# mux10-1.net
KiCad netlist of a schematic drawn in Altium Designer
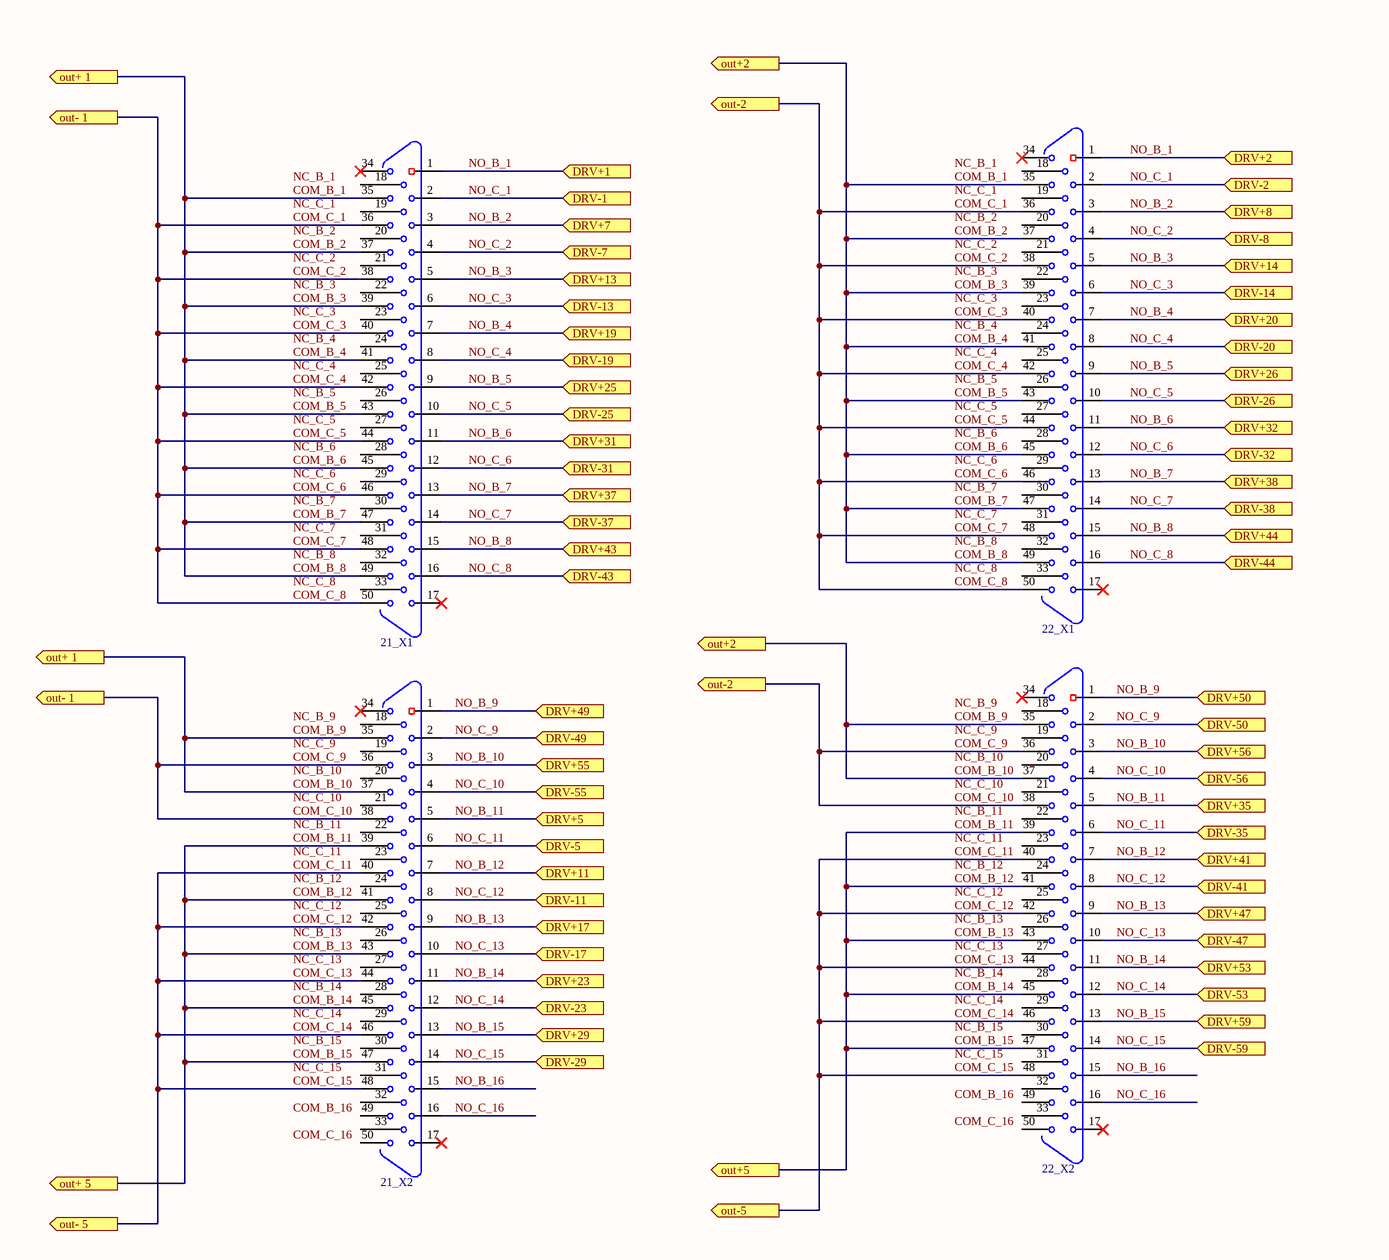
[diagram p0: mux10-1.SchDoc, left]
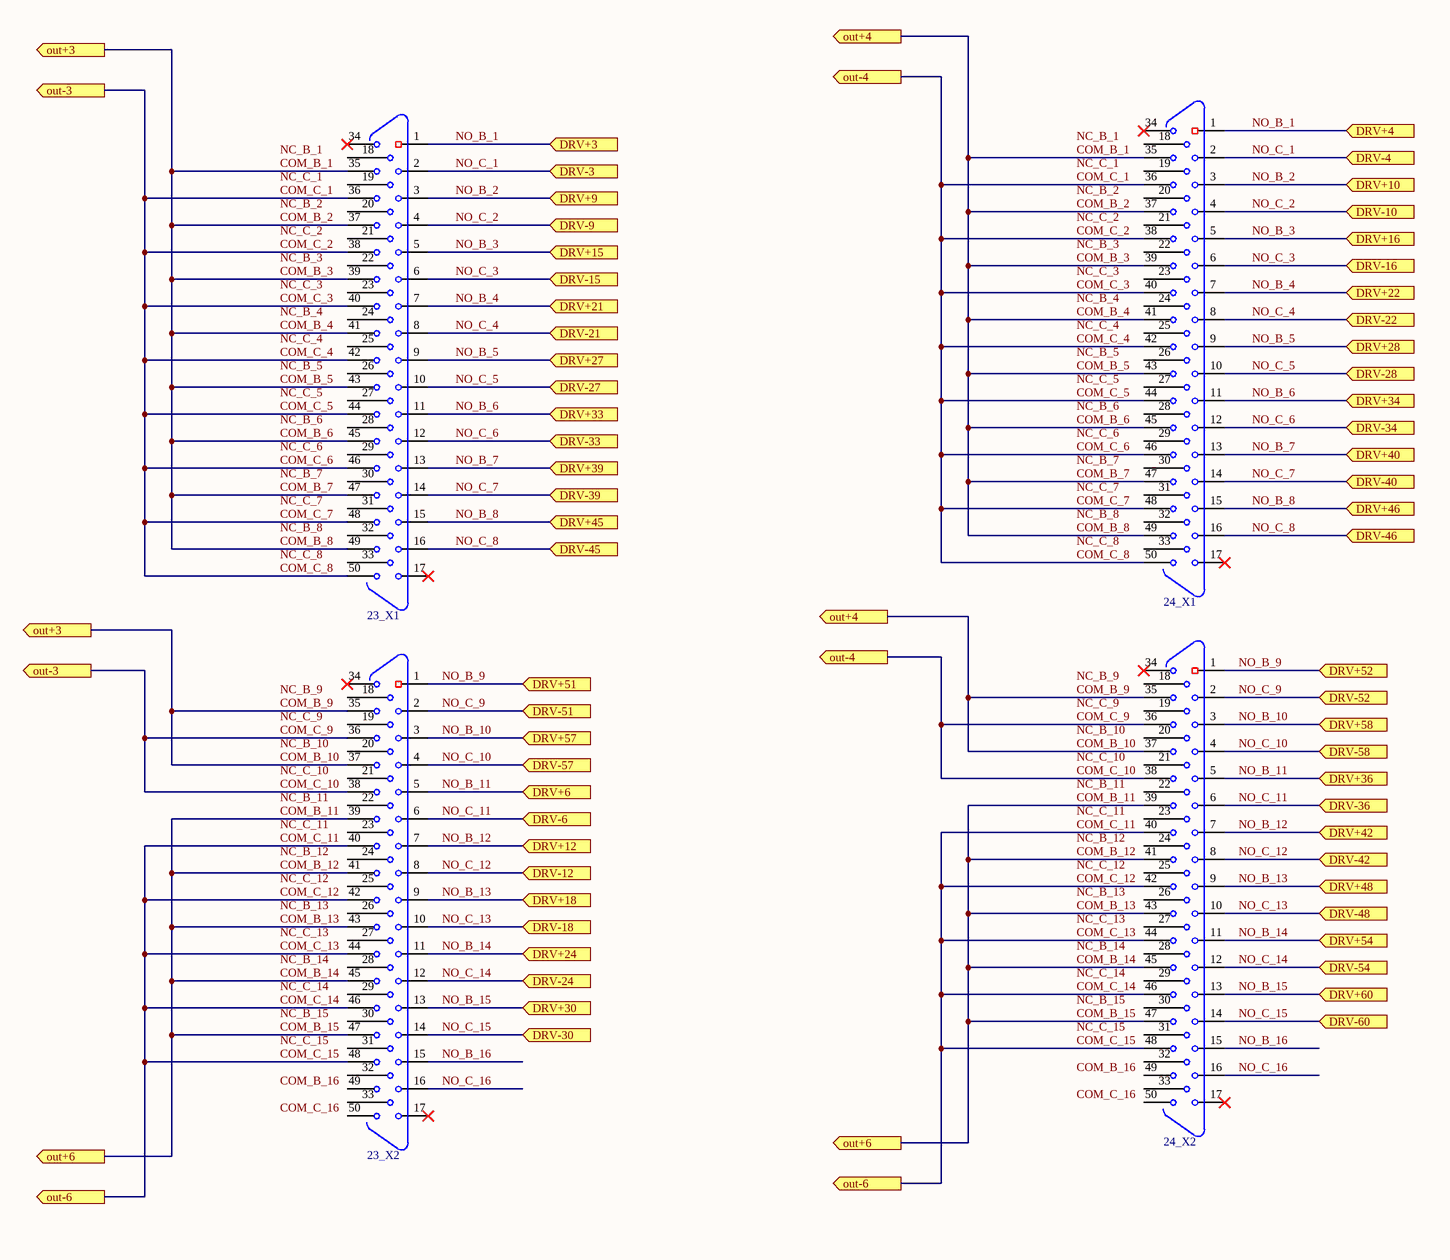
[diagram p1: mux10-1.SchDoc, right]

(export (version "E")
  (design (tool "Eeschema 10.0.6"))
  (components
    (comp (ref "21_X1") (value "DB50") (footprint "DB50_RA") (libsource (lib "WIRE") (part "DB50")))
    (comp (ref "21_X2") (value "DB50") (footprint "DB50_RA") (libsource (lib "WIRE") (part "DB50")))
    (comp (ref "22_X1") (value "DB50") (footprint "DB50_RA") (libsource (lib "WIRE") (part "DB50")))
    (comp (ref "22_X2") (value "DB50") (footprint "DB50_RA") (libsource (lib "WIRE") (part "DB50")))
    (comp (ref "23_X1") (value "DB50") (footprint "DB50_RA") (libsource (lib "WIRE") (part "DB50")))
    (comp (ref "23_X2") (value "DB50") (footprint "DB50_RA") (libsource (lib "WIRE") (part "DB50")))
    (comp (ref "24_X1") (value "DB50") (footprint "DB50_RA") (libsource (lib "WIRE") (part "DB50")))
    (comp (ref "24_X2") (value "DB50") (footprint "DB50_RA") (libsource (lib "WIRE") (part "DB50")))
  )
  (nets
    (net (code "1") (name "/COM_B_1") (class "Default")
      (node (ref "21_X1") (pin "35") (pinfunction "35_35") (pintype "passive"))
      (node (ref "21_X1") (pin "37") (pinfunction "37_37") (pintype "passive"))
      (node (ref "21_X1") (pin "39") (pinfunction "39_39") (pintype "passive"))
      (node (ref "21_X1") (pin "41") (pinfunction "41_41") (pintype "passive"))
      (node (ref "21_X1") (pin "43") (pinfunction "43_43") (pintype "passive"))
      (node (ref "21_X1") (pin "45") (pinfunction "45_45") (pintype "passive"))
      (node (ref "21_X1") (pin "47") (pinfunction "47_47") (pintype "passive"))
      (node (ref "21_X1") (pin "49") (pinfunction "49_49") (pintype "passive"))
      (node (ref "21_X2") (pin "35") (pinfunction "35_35") (pintype "passive"))
      (node (ref "21_X2") (pin "37") (pinfunction "37_37") (pintype "passive"))
      (node (ref "22_X1") (pin "35") (pinfunction "35_35") (pintype "passive"))
      (node (ref "22_X1") (pin "37") (pinfunction "37_37") (pintype "passive"))
      (node (ref "22_X1") (pin "39") (pinfunction "39_39") (pintype "passive"))
      (node (ref "22_X1") (pin "41") (pinfunction "41_41") (pintype "passive"))
      (node (ref "22_X1") (pin "43") (pinfunction "43_43") (pintype "passive"))
      (node (ref "22_X1") (pin "45") (pinfunction "45_45") (pintype "passive"))
      (node (ref "22_X1") (pin "47") (pinfunction "47_47") (pintype "passive"))
      (node (ref "22_X1") (pin "49") (pinfunction "49_49") (pintype "passive"))
      (node (ref "22_X2") (pin "35") (pinfunction "35_35") (pintype "passive"))
      (node (ref "22_X2") (pin "37") (pinfunction "37_37") (pintype "passive"))
      (node (ref "23_X1") (pin "35") (pinfunction "35_35") (pintype "passive"))
      (node (ref "23_X1") (pin "37") (pinfunction "37_37") (pintype "passive"))
      (node (ref "23_X1") (pin "39") (pinfunction "39_39") (pintype "passive"))
      (node (ref "23_X1") (pin "41") (pinfunction "41_41") (pintype "passive"))
      (node (ref "23_X1") (pin "43") (pinfunction "43_43") (pintype "passive"))
      (node (ref "23_X1") (pin "45") (pinfunction "45_45") (pintype "passive"))
      (node (ref "23_X1") (pin "47") (pinfunction "47_47") (pintype "passive"))
      (node (ref "23_X1") (pin "49") (pinfunction "49_49") (pintype "passive"))
      (node (ref "23_X2") (pin "35") (pinfunction "35_35") (pintype "passive"))
      (node (ref "23_X2") (pin "37") (pinfunction "37_37") (pintype "passive"))
      (node (ref "24_X1") (pin "35") (pinfunction "35_35") (pintype "passive"))
      (node (ref "24_X1") (pin "37") (pinfunction "37_37") (pintype "passive"))
      (node (ref "24_X1") (pin "39") (pinfunction "39_39") (pintype "passive"))
      (node (ref "24_X1") (pin "41") (pinfunction "41_41") (pintype "passive"))
      (node (ref "24_X1") (pin "43") (pinfunction "43_43") (pintype "passive"))
      (node (ref "24_X1") (pin "45") (pinfunction "45_45") (pintype "passive"))
      (node (ref "24_X1") (pin "47") (pinfunction "47_47") (pintype "passive"))
      (node (ref "24_X1") (pin "49") (pinfunction "49_49") (pintype "passive"))
      (node (ref "24_X2") (pin "35") (pinfunction "35_35") (pintype "passive"))
      (node (ref "24_X2") (pin "37") (pinfunction "37_37") (pintype "passive"))
    )
    (net (code "2") (name "/COM_B_11") (class "Default")
      (node (ref "21_X2") (pin "39") (pinfunction "39_39") (pintype "passive"))
      (node (ref "21_X2") (pin "41") (pinfunction "41_41") (pintype "passive"))
      (node (ref "21_X2") (pin "43") (pinfunction "43_43") (pintype "passive"))
      (node (ref "21_X2") (pin "45") (pinfunction "45_45") (pintype "passive"))
      (node (ref "21_X2") (pin "47") (pinfunction "47_47") (pintype "passive"))
      (node (ref "22_X2") (pin "39") (pinfunction "39_39") (pintype "passive"))
      (node (ref "22_X2") (pin "41") (pinfunction "41_41") (pintype "passive"))
      (node (ref "22_X2") (pin "43") (pinfunction "43_43") (pintype "passive"))
      (node (ref "22_X2") (pin "45") (pinfunction "45_45") (pintype "passive"))
      (node (ref "22_X2") (pin "47") (pinfunction "47_47") (pintype "passive"))
      (node (ref "23_X2") (pin "39") (pinfunction "39_39") (pintype "passive"))
      (node (ref "23_X2") (pin "41") (pinfunction "41_41") (pintype "passive"))
      (node (ref "23_X2") (pin "43") (pinfunction "43_43") (pintype "passive"))
      (node (ref "23_X2") (pin "45") (pinfunction "45_45") (pintype "passive"))
      (node (ref "23_X2") (pin "47") (pinfunction "47_47") (pintype "passive"))
      (node (ref "24_X2") (pin "39") (pinfunction "39_39") (pintype "passive"))
      (node (ref "24_X2") (pin "41") (pinfunction "41_41") (pintype "passive"))
      (node (ref "24_X2") (pin "43") (pinfunction "43_43") (pintype "passive"))
      (node (ref "24_X2") (pin "45") (pinfunction "45_45") (pintype "passive"))
      (node (ref "24_X2") (pin "47") (pinfunction "47_47") (pintype "passive"))
    )
    (net (code "4") (name "/COM_C_1") (class "Default")
      (node (ref "21_X1") (pin "36") (pinfunction "36_36") (pintype "passive"))
      (node (ref "21_X1") (pin "38") (pinfunction "38_38") (pintype "passive"))
      (node (ref "21_X1") (pin "40") (pinfunction "40_40") (pintype "passive"))
      (node (ref "21_X1") (pin "42") (pinfunction "42_42") (pintype "passive"))
      (node (ref "21_X1") (pin "44") (pinfunction "44_44") (pintype "passive"))
      (node (ref "21_X1") (pin "46") (pinfunction "46_46") (pintype "passive"))
      (node (ref "21_X1") (pin "48") (pinfunction "48_48") (pintype "passive"))
      (node (ref "21_X1") (pin "50") (pinfunction "50_50") (pintype "passive"))
      (node (ref "21_X2") (pin "36") (pinfunction "36_36") (pintype "passive"))
      (node (ref "21_X2") (pin "38") (pinfunction "38_38") (pintype "passive"))
      (node (ref "22_X1") (pin "36") (pinfunction "36_36") (pintype "passive"))
      (node (ref "22_X1") (pin "38") (pinfunction "38_38") (pintype "passive"))
      (node (ref "22_X1") (pin "40") (pinfunction "40_40") (pintype "passive"))
      (node (ref "22_X1") (pin "42") (pinfunction "42_42") (pintype "passive"))
      (node (ref "22_X1") (pin "44") (pinfunction "44_44") (pintype "passive"))
      (node (ref "22_X1") (pin "46") (pinfunction "46_46") (pintype "passive"))
      (node (ref "22_X1") (pin "48") (pinfunction "48_48") (pintype "passive"))
      (node (ref "22_X1") (pin "50") (pinfunction "50_50") (pintype "passive"))
      (node (ref "22_X2") (pin "36") (pinfunction "36_36") (pintype "passive"))
      (node (ref "22_X2") (pin "38") (pinfunction "38_38") (pintype "passive"))
      (node (ref "23_X1") (pin "36") (pinfunction "36_36") (pintype "passive"))
      (node (ref "23_X1") (pin "38") (pinfunction "38_38") (pintype "passive"))
      (node (ref "23_X1") (pin "40") (pinfunction "40_40") (pintype "passive"))
      (node (ref "23_X1") (pin "42") (pinfunction "42_42") (pintype "passive"))
      (node (ref "23_X1") (pin "44") (pinfunction "44_44") (pintype "passive"))
      (node (ref "23_X1") (pin "46") (pinfunction "46_46") (pintype "passive"))
      (node (ref "23_X1") (pin "48") (pinfunction "48_48") (pintype "passive"))
      (node (ref "23_X1") (pin "50") (pinfunction "50_50") (pintype "passive"))
      (node (ref "23_X2") (pin "36") (pinfunction "36_36") (pintype "passive"))
      (node (ref "23_X2") (pin "38") (pinfunction "38_38") (pintype "passive"))
      (node (ref "24_X1") (pin "36") (pinfunction "36_36") (pintype "passive"))
      (node (ref "24_X1") (pin "38") (pinfunction "38_38") (pintype "passive"))
      (node (ref "24_X1") (pin "40") (pinfunction "40_40") (pintype "passive"))
      (node (ref "24_X1") (pin "42") (pinfunction "42_42") (pintype "passive"))
      (node (ref "24_X1") (pin "44") (pinfunction "44_44") (pintype "passive"))
      (node (ref "24_X1") (pin "46") (pinfunction "46_46") (pintype "passive"))
      (node (ref "24_X1") (pin "48") (pinfunction "48_48") (pintype "passive"))
      (node (ref "24_X1") (pin "50") (pinfunction "50_50") (pintype "passive"))
      (node (ref "24_X2") (pin "36") (pinfunction "36_36") (pintype "passive"))
      (node (ref "24_X2") (pin "38") (pinfunction "38_38") (pintype "passive"))
    )
    (net (code "5") (name "/COM_C_11") (class "Default")
      (node (ref "21_X2") (pin "40") (pinfunction "40_40") (pintype "passive"))
      (node (ref "21_X2") (pin "42") (pinfunction "42_42") (pintype "passive"))
      (node (ref "21_X2") (pin "44") (pinfunction "44_44") (pintype "passive"))
      (node (ref "21_X2") (pin "46") (pinfunction "46_46") (pintype "passive"))
      (node (ref "21_X2") (pin "48") (pinfunction "48_48") (pintype "passive"))
      (node (ref "22_X2") (pin "40") (pinfunction "40_40") (pintype "passive"))
      (node (ref "22_X2") (pin "42") (pinfunction "42_42") (pintype "passive"))
      (node (ref "22_X2") (pin "44") (pinfunction "44_44") (pintype "passive"))
      (node (ref "22_X2") (pin "46") (pinfunction "46_46") (pintype "passive"))
      (node (ref "22_X2") (pin "48") (pinfunction "48_48") (pintype "passive"))
      (node (ref "23_X2") (pin "40") (pinfunction "40_40") (pintype "passive"))
      (node (ref "23_X2") (pin "42") (pinfunction "42_42") (pintype "passive"))
      (node (ref "23_X2") (pin "44") (pinfunction "44_44") (pintype "passive"))
      (node (ref "23_X2") (pin "46") (pinfunction "46_46") (pintype "passive"))
      (node (ref "23_X2") (pin "48") (pinfunction "48_48") (pintype "passive"))
      (node (ref "24_X2") (pin "40") (pinfunction "40_40") (pintype "passive"))
      (node (ref "24_X2") (pin "42") (pinfunction "42_42") (pintype "passive"))
      (node (ref "24_X2") (pin "44") (pinfunction "44_44") (pintype "passive"))
      (node (ref "24_X2") (pin "46") (pinfunction "46_46") (pintype "passive"))
      (node (ref "24_X2") (pin "48") (pinfunction "48_48") (pintype "passive"))
    )
    (net (code "37") (name "/NO_B_1") (class "Default")
      (node (ref "21_X1") (pin "1") (pinfunction "1_1") (pintype "passive"))
      (node (ref "22_X1") (pin "1") (pinfunction "1_1") (pintype "passive"))
      (node (ref "23_X1") (pin "1") (pinfunction "1_1") (pintype "passive"))
      (node (ref "24_X1") (pin "1") (pinfunction "1_1") (pintype "passive"))
    )
    (net (code "38") (name "/NO_B_2") (class "Default")
      (node (ref "21_X1") (pin "3") (pinfunction "3_3") (pintype "passive"))
      (node (ref "22_X1") (pin "3") (pinfunction "3_3") (pintype "passive"))
      (node (ref "23_X1") (pin "3") (pinfunction "3_3") (pintype "passive"))
      (node (ref "24_X1") (pin "3") (pinfunction "3_3") (pintype "passive"))
    )
    (net (code "39") (name "/NO_B_3") (class "Default")
      (node (ref "21_X1") (pin "5") (pinfunction "2_5") (pintype "passive"))
      (node (ref "22_X1") (pin "5") (pinfunction "2_5") (pintype "passive"))
      (node (ref "23_X1") (pin "5") (pinfunction "2_5") (pintype "passive"))
      (node (ref "24_X1") (pin "5") (pinfunction "2_5") (pintype "passive"))
    )
    (net (code "40") (name "/NO_B_4") (class "Default")
      (node (ref "21_X1") (pin "7") (pinfunction "7_7") (pintype "passive"))
      (node (ref "22_X1") (pin "7") (pinfunction "7_7") (pintype "passive"))
      (node (ref "23_X1") (pin "7") (pinfunction "7_7") (pintype "passive"))
      (node (ref "24_X1") (pin "7") (pinfunction "7_7") (pintype "passive"))
    )
    (net (code "41") (name "/NO_B_5") (class "Default")
      (node (ref "21_X1") (pin "9") (pinfunction "4_9") (pintype "passive"))
      (node (ref "22_X1") (pin "9") (pinfunction "4_9") (pintype "passive"))
      (node (ref "23_X1") (pin "9") (pinfunction "4_9") (pintype "passive"))
      (node (ref "24_X1") (pin "9") (pinfunction "4_9") (pintype "passive"))
    )
    (net (code "42") (name "/NO_B_6") (class "Default")
      (node (ref "21_X1") (pin "11") (pinfunction "11_11") (pintype "passive"))
      (node (ref "22_X1") (pin "11") (pinfunction "11_11") (pintype "passive"))
      (node (ref "23_X1") (pin "11") (pinfunction "11_11") (pintype "passive"))
      (node (ref "24_X1") (pin "11") (pinfunction "11_11") (pintype "passive"))
    )
    (net (code "43") (name "/NO_B_7") (class "Default")
      (node (ref "21_X1") (pin "13") (pinfunction "13_13") (pintype "passive"))
      (node (ref "22_X1") (pin "13") (pinfunction "13_13") (pintype "passive"))
      (node (ref "23_X1") (pin "13") (pinfunction "13_13") (pintype "passive"))
      (node (ref "24_X1") (pin "13") (pinfunction "13_13") (pintype "passive"))
    )
    (net (code "44") (name "/NO_B_8") (class "Default")
      (node (ref "21_X1") (pin "15") (pinfunction "15_15") (pintype "passive"))
      (node (ref "22_X1") (pin "15") (pinfunction "15_15") (pintype "passive"))
      (node (ref "23_X1") (pin "15") (pinfunction "15_15") (pintype "passive"))
      (node (ref "24_X1") (pin "15") (pinfunction "15_15") (pintype "passive"))
    )
    (net (code "45") (name "/NO_B_9") (class "Default")
      (node (ref "21_X2") (pin "1") (pinfunction "1_1") (pintype "passive"))
      (node (ref "22_X2") (pin "1") (pinfunction "1_1") (pintype "passive"))
      (node (ref "23_X2") (pin "1") (pinfunction "1_1") (pintype "passive"))
      (node (ref "24_X2") (pin "1") (pinfunction "1_1") (pintype "passive"))
    )
    (net (code "46") (name "/NO_B_10") (class "Default")
      (node (ref "21_X2") (pin "3") (pinfunction "3_3") (pintype "passive"))
      (node (ref "22_X2") (pin "3") (pinfunction "3_3") (pintype "passive"))
      (node (ref "23_X2") (pin "3") (pinfunction "3_3") (pintype "passive"))
      (node (ref "24_X2") (pin "3") (pinfunction "3_3") (pintype "passive"))
    )
    (net (code "47") (name "/NO_B_11") (class "Default")
      (node (ref "21_X2") (pin "5") (pinfunction "2_5") (pintype "passive"))
      (node (ref "22_X2") (pin "5") (pinfunction "2_5") (pintype "passive"))
      (node (ref "23_X2") (pin "5") (pinfunction "2_5") (pintype "passive"))
      (node (ref "24_X2") (pin "5") (pinfunction "2_5") (pintype "passive"))
    )
    (net (code "48") (name "/NO_B_12") (class "Default")
      (node (ref "21_X2") (pin "7") (pinfunction "7_7") (pintype "passive"))
      (node (ref "22_X2") (pin "7") (pinfunction "7_7") (pintype "passive"))
      (node (ref "23_X2") (pin "7") (pinfunction "7_7") (pintype "passive"))
      (node (ref "24_X2") (pin "7") (pinfunction "7_7") (pintype "passive"))
    )
    (net (code "49") (name "/NO_B_13") (class "Default")
      (node (ref "21_X2") (pin "9") (pinfunction "4_9") (pintype "passive"))
      (node (ref "22_X2") (pin "9") (pinfunction "4_9") (pintype "passive"))
      (node (ref "23_X2") (pin "9") (pinfunction "4_9") (pintype "passive"))
      (node (ref "24_X2") (pin "9") (pinfunction "4_9") (pintype "passive"))
    )
    (net (code "50") (name "/NO_B_14") (class "Default")
      (node (ref "21_X2") (pin "11") (pinfunction "11_11") (pintype "passive"))
      (node (ref "22_X2") (pin "11") (pinfunction "11_11") (pintype "passive"))
      (node (ref "23_X2") (pin "11") (pinfunction "11_11") (pintype "passive"))
      (node (ref "24_X2") (pin "11") (pinfunction "11_11") (pintype "passive"))
    )
    (net (code "51") (name "/NO_B_15") (class "Default")
      (node (ref "21_X2") (pin "13") (pinfunction "13_13") (pintype "passive"))
      (node (ref "22_X2") (pin "13") (pinfunction "13_13") (pintype "passive"))
      (node (ref "23_X2") (pin "13") (pinfunction "13_13") (pintype "passive"))
      (node (ref "24_X2") (pin "13") (pinfunction "13_13") (pintype "passive"))
    )
    (net (code "52") (name "/NO_B_16") (class "Default")
      (node (ref "21_X2") (pin "15") (pinfunction "15_15") (pintype "passive"))
      (node (ref "22_X2") (pin "15") (pinfunction "15_15") (pintype "passive"))
      (node (ref "23_X2") (pin "15") (pinfunction "15_15") (pintype "passive"))
      (node (ref "24_X2") (pin "15") (pinfunction "15_15") (pintype "passive"))
    )
    (net (code "53") (name "/NO_C_1") (class "Default")
      (node (ref "21_X1") (pin "2") (pinfunction "2_2") (pintype "passive"))
      (node (ref "22_X1") (pin "2") (pinfunction "2_2") (pintype "passive"))
      (node (ref "23_X1") (pin "2") (pinfunction "2_2") (pintype "passive"))
      (node (ref "24_X1") (pin "2") (pinfunction "2_2") (pintype "passive"))
    )
    (net (code "54") (name "/NO_C_2") (class "Default")
      (node (ref "21_X1") (pin "4") (pinfunction "4_4") (pintype "passive"))
      (node (ref "22_X1") (pin "4") (pinfunction "4_4") (pintype "passive"))
      (node (ref "23_X1") (pin "4") (pinfunction "4_4") (pintype "passive"))
      (node (ref "24_X1") (pin "4") (pinfunction "4_4") (pintype "passive"))
    )
    (net (code "55") (name "/NO_C_3") (class "Default")
      (node (ref "21_X1") (pin "6") (pinfunction "6_6") (pintype "passive"))
      (node (ref "22_X1") (pin "6") (pinfunction "6_6") (pintype "passive"))
      (node (ref "23_X1") (pin "6") (pinfunction "6_6") (pintype "passive"))
      (node (ref "24_X1") (pin "6") (pinfunction "6_6") (pintype "passive"))
    )
    (net (code "56") (name "/NO_C_4") (class "Default")
      (node (ref "21_X1") (pin "8") (pinfunction "8_8") (pintype "passive"))
      (node (ref "22_X1") (pin "8") (pinfunction "8_8") (pintype "passive"))
      (node (ref "23_X1") (pin "8") (pinfunction "8_8") (pintype "passive"))
      (node (ref "24_X1") (pin "8") (pinfunction "8_8") (pintype "passive"))
    )
    (net (code "57") (name "/NO_C_5") (class "Default")
      (node (ref "21_X1") (pin "10") (pinfunction "10_10") (pintype "passive"))
      (node (ref "22_X1") (pin "10") (pinfunction "10_10") (pintype "passive"))
      (node (ref "23_X1") (pin "10") (pinfunction "10_10") (pintype "passive"))
      (node (ref "24_X1") (pin "10") (pinfunction "10_10") (pintype "passive"))
    )
    (net (code "58") (name "/NO_C_6") (class "Default")
      (node (ref "21_X1") (pin "12") (pinfunction "12_12") (pintype "passive"))
      (node (ref "22_X1") (pin "12") (pinfunction "12_12") (pintype "passive"))
      (node (ref "23_X1") (pin "12") (pinfunction "12_12") (pintype "passive"))
      (node (ref "24_X1") (pin "12") (pinfunction "12_12") (pintype "passive"))
    )
    (net (code "59") (name "/NO_C_7") (class "Default")
      (node (ref "21_X1") (pin "14") (pinfunction "14_14") (pintype "passive"))
      (node (ref "22_X1") (pin "14") (pinfunction "14_14") (pintype "passive"))
      (node (ref "23_X1") (pin "14") (pinfunction "14_14") (pintype "passive"))
      (node (ref "24_X1") (pin "14") (pinfunction "14_14") (pintype "passive"))
    )
    (net (code "60") (name "/NO_C_8") (class "Default")
      (node (ref "21_X1") (pin "16") (pinfunction "16_16") (pintype "passive"))
      (node (ref "22_X1") (pin "16") (pinfunction "16_16") (pintype "passive"))
      (node (ref "23_X1") (pin "16") (pinfunction "16_16") (pintype "passive"))
      (node (ref "24_X1") (pin "16") (pinfunction "16_16") (pintype "passive"))
    )
    (net (code "61") (name "/NO_C_9") (class "Default")
      (node (ref "21_X2") (pin "2") (pinfunction "2_2") (pintype "passive"))
      (node (ref "22_X2") (pin "2") (pinfunction "2_2") (pintype "passive"))
      (node (ref "23_X2") (pin "2") (pinfunction "2_2") (pintype "passive"))
      (node (ref "24_X2") (pin "2") (pinfunction "2_2") (pintype "passive"))
    )
    (net (code "62") (name "/NO_C_10") (class "Default")
      (node (ref "21_X2") (pin "4") (pinfunction "4_4") (pintype "passive"))
      (node (ref "22_X2") (pin "4") (pinfunction "4_4") (pintype "passive"))
      (node (ref "23_X2") (pin "4") (pinfunction "4_4") (pintype "passive"))
      (node (ref "24_X2") (pin "4") (pinfunction "4_4") (pintype "passive"))
    )
    (net (code "63") (name "/NO_C_11") (class "Default")
      (node (ref "21_X2") (pin "6") (pinfunction "6_6") (pintype "passive"))
      (node (ref "22_X2") (pin "6") (pinfunction "6_6") (pintype "passive"))
      (node (ref "23_X2") (pin "6") (pinfunction "6_6") (pintype "passive"))
      (node (ref "24_X2") (pin "6") (pinfunction "6_6") (pintype "passive"))
    )
    (net (code "64") (name "/NO_C_12") (class "Default")
      (node (ref "21_X2") (pin "8") (pinfunction "8_8") (pintype "passive"))
      (node (ref "22_X2") (pin "8") (pinfunction "8_8") (pintype "passive"))
      (node (ref "23_X2") (pin "8") (pinfunction "8_8") (pintype "passive"))
      (node (ref "24_X2") (pin "8") (pinfunction "8_8") (pintype "passive"))
    )
    (net (code "65") (name "/NO_C_13") (class "Default")
      (node (ref "21_X2") (pin "10") (pinfunction "10_10") (pintype "passive"))
      (node (ref "22_X2") (pin "10") (pinfunction "10_10") (pintype "passive"))
      (node (ref "23_X2") (pin "10") (pinfunction "10_10") (pintype "passive"))
      (node (ref "24_X2") (pin "10") (pinfunction "10_10") (pintype "passive"))
    )
    (net (code "66") (name "/NO_C_14") (class "Default")
      (node (ref "21_X2") (pin "12") (pinfunction "12_12") (pintype "passive"))
      (node (ref "22_X2") (pin "12") (pinfunction "12_12") (pintype "passive"))
      (node (ref "23_X2") (pin "12") (pinfunction "12_12") (pintype "passive"))
      (node (ref "24_X2") (pin "12") (pinfunction "12_12") (pintype "passive"))
    )
    (net (code "67") (name "/NO_C_15") (class "Default")
      (node (ref "21_X2") (pin "14") (pinfunction "14_14") (pintype "passive"))
      (node (ref "22_X2") (pin "14") (pinfunction "14_14") (pintype "passive"))
      (node (ref "23_X2") (pin "14") (pinfunction "14_14") (pintype "passive"))
      (node (ref "24_X2") (pin "14") (pinfunction "14_14") (pintype "passive"))
    )
    (net (code "68") (name "/NO_C_16") (class "Default")
      (node (ref "21_X2") (pin "16") (pinfunction "16_16") (pintype "passive"))
      (node (ref "22_X2") (pin "16") (pinfunction "16_16") (pintype "passive"))
      (node (ref "23_X2") (pin "16") (pinfunction "16_16") (pintype "passive"))
      (node (ref "24_X2") (pin "16") (pinfunction "16_16") (pintype "passive"))
    )
    (net (code "69") (name "unconnected-(21_X1-3-Pad25)") (class "Default")
      (node (ref "21_X1") (pin "25") (pinfunction "3_25") (pintype "passive"))
    )
    (net (code "70") (name "unconnected-(21_X1-7-Pad24)") (class "Default")
      (node (ref "21_X1") (pin "24") (pinfunction "7_24") (pintype "passive"))
    )
    (net (code "71") (name "unconnected-(21_X1-Pad17)") (class "Default")
      (node (ref "21_X1") (pin "17") (pinfunction "17_17") (pintype "passive+no_connect"))
    )
    (net (code "72") (name "unconnected-(21_X1-Pad18)") (class "Default")
      (node (ref "21_X1") (pin "18") (pinfunction "18_18") (pintype "passive"))
    )
    (net (code "73") (name "unconnected-(21_X1-Pad19)") (class "Default")
      (node (ref "21_X1") (pin "19") (pinfunction "19_19") (pintype "passive"))
    )
    (net (code "74") (name "unconnected-(21_X1-Pad20)") (class "Default")
      (node (ref "21_X1") (pin "20") (pinfunction "20_20") (pintype "passive"))
    )
    (net (code "75") (name "unconnected-(21_X1-Pad21)") (class "Default")
      (node (ref "21_X1") (pin "21") (pinfunction "21_21") (pintype "passive"))
    )
    (net (code "76") (name "unconnected-(21_X1-Pad22)") (class "Default")
      (node (ref "21_X1") (pin "22") (pinfunction "22_22") (pintype "passive"))
    )
    (net (code "77") (name "unconnected-(21_X1-Pad23)") (class "Default")
      (node (ref "21_X1") (pin "23") (pinfunction "23_23") (pintype "passive"))
    )
    (net (code "78") (name "unconnected-(21_X1-Pad26)") (class "Default")
      (node (ref "21_X1") (pin "26") (pinfunction "26_26") (pintype "passive"))
    )
    (net (code "79") (name "unconnected-(21_X1-Pad27)") (class "Default")
      (node (ref "21_X1") (pin "27") (pinfunction "27_27") (pintype "passive"))
    )
    (net (code "80") (name "unconnected-(21_X1-Pad28)") (class "Default")
      (node (ref "21_X1") (pin "28") (pinfunction "28_28") (pintype "passive"))
    )
    (net (code "81") (name "unconnected-(21_X1-Pad29)") (class "Default")
      (node (ref "21_X1") (pin "29") (pinfunction "29_29") (pintype "passive"))
    )
    (net (code "82") (name "unconnected-(21_X1-Pad30)") (class "Default")
      (node (ref "21_X1") (pin "30") (pinfunction "30_30") (pintype "passive"))
    )
    (net (code "83") (name "unconnected-(21_X1-Pad31)") (class "Default")
      (node (ref "21_X1") (pin "31") (pinfunction "31_31") (pintype "passive"))
    )
    (net (code "84") (name "unconnected-(21_X1-Pad32)") (class "Default")
      (node (ref "21_X1") (pin "32") (pinfunction "32_32") (pintype "passive"))
    )
    (net (code "85") (name "unconnected-(21_X1-Pad33)") (class "Default")
      (node (ref "21_X1") (pin "33") (pinfunction "33_33") (pintype "passive"))
    )
    (net (code "86") (name "unconnected-(21_X1-Pad34)") (class "Default")
      (node (ref "21_X1") (pin "34") (pinfunction "34_34") (pintype "passive+no_connect"))
    )
    (net (code "87") (name "unconnected-(21_X2-3-Pad25)") (class "Default")
      (node (ref "21_X2") (pin "25") (pinfunction "3_25") (pintype "passive"))
    )
    (net (code "88") (name "unconnected-(21_X2-7-Pad24)") (class "Default")
      (node (ref "21_X2") (pin "24") (pinfunction "7_24") (pintype "passive"))
    )
    (net (code "89") (name "unconnected-(21_X2-Pad17)") (class "Default")
      (node (ref "21_X2") (pin "17") (pinfunction "17_17") (pintype "passive+no_connect"))
    )
    (net (code "90") (name "unconnected-(21_X2-Pad18)") (class "Default")
      (node (ref "21_X2") (pin "18") (pinfunction "18_18") (pintype "passive"))
    )
    (net (code "91") (name "unconnected-(21_X2-Pad19)") (class "Default")
      (node (ref "21_X2") (pin "19") (pinfunction "19_19") (pintype "passive"))
    )
    (net (code "92") (name "unconnected-(21_X2-Pad20)") (class "Default")
      (node (ref "21_X2") (pin "20") (pinfunction "20_20") (pintype "passive"))
    )
    (net (code "93") (name "unconnected-(21_X2-Pad21)") (class "Default")
      (node (ref "21_X2") (pin "21") (pinfunction "21_21") (pintype "passive"))
    )
    (net (code "94") (name "unconnected-(21_X2-Pad22)") (class "Default")
      (node (ref "21_X2") (pin "22") (pinfunction "22_22") (pintype "passive"))
    )
    (net (code "95") (name "unconnected-(21_X2-Pad23)") (class "Default")
      (node (ref "21_X2") (pin "23") (pinfunction "23_23") (pintype "passive"))
    )
    (net (code "96") (name "unconnected-(21_X2-Pad26)") (class "Default")
      (node (ref "21_X2") (pin "26") (pinfunction "26_26") (pintype "passive"))
    )
    (net (code "97") (name "unconnected-(21_X2-Pad27)") (class "Default")
      (node (ref "21_X2") (pin "27") (pinfunction "27_27") (pintype "passive"))
    )
    (net (code "98") (name "unconnected-(21_X2-Pad28)") (class "Default")
      (node (ref "21_X2") (pin "28") (pinfunction "28_28") (pintype "passive"))
    )
    (net (code "99") (name "unconnected-(21_X2-Pad29)") (class "Default")
      (node (ref "21_X2") (pin "29") (pinfunction "29_29") (pintype "passive"))
    )
    (net (code "100") (name "unconnected-(21_X2-Pad30)") (class "Default")
      (node (ref "21_X2") (pin "30") (pinfunction "30_30") (pintype "passive"))
    )
    (net (code "101") (name "unconnected-(21_X2-Pad31)") (class "Default")
      (node (ref "21_X2") (pin "31") (pinfunction "31_31") (pintype "passive"))
    )
    (net (code "102") (name "unconnected-(21_X2-Pad32)") (class "Default")
      (node (ref "21_X2") (pin "32") (pinfunction "32_32") (pintype "passive"))
    )
    (net (code "103") (name "unconnected-(21_X2-Pad33)") (class "Default")
      (node (ref "21_X2") (pin "33") (pinfunction "33_33") (pintype "passive"))
    )
    (net (code "104") (name "unconnected-(21_X2-Pad34)") (class "Default")
      (node (ref "21_X2") (pin "34") (pinfunction "34_34") (pintype "passive+no_connect"))
    )
    (net (code "105") (name "unconnected-(21_X2-Pad49)") (class "Default")
      (node (ref "21_X2") (pin "49") (pinfunction "49_49") (pintype "passive"))
    )
    (net (code "106") (name "unconnected-(21_X2-Pad50)") (class "Default")
      (node (ref "21_X2") (pin "50") (pinfunction "50_50") (pintype "passive"))
    )
    (net (code "107") (name "unconnected-(22_X1-3-Pad25)") (class "Default")
      (node (ref "22_X1") (pin "25") (pinfunction "3_25") (pintype "passive"))
    )
    (net (code "108") (name "unconnected-(22_X1-7-Pad24)") (class "Default")
      (node (ref "22_X1") (pin "24") (pinfunction "7_24") (pintype "passive"))
    )
    (net (code "109") (name "unconnected-(22_X1-Pad17)") (class "Default")
      (node (ref "22_X1") (pin "17") (pinfunction "17_17") (pintype "passive+no_connect"))
    )
    (net (code "110") (name "unconnected-(22_X1-Pad18)") (class "Default")
      (node (ref "22_X1") (pin "18") (pinfunction "18_18") (pintype "passive"))
    )
    (net (code "111") (name "unconnected-(22_X1-Pad19)") (class "Default")
      (node (ref "22_X1") (pin "19") (pinfunction "19_19") (pintype "passive"))
    )
    (net (code "112") (name "unconnected-(22_X1-Pad20)") (class "Default")
      (node (ref "22_X1") (pin "20") (pinfunction "20_20") (pintype "passive"))
    )
    (net (code "113") (name "unconnected-(22_X1-Pad21)") (class "Default")
      (node (ref "22_X1") (pin "21") (pinfunction "21_21") (pintype "passive"))
    )
    (net (code "114") (name "unconnected-(22_X1-Pad22)") (class "Default")
      (node (ref "22_X1") (pin "22") (pinfunction "22_22") (pintype "passive"))
    )
    (net (code "115") (name "unconnected-(22_X1-Pad23)") (class "Default")
      (node (ref "22_X1") (pin "23") (pinfunction "23_23") (pintype "passive"))
    )
    (net (code "116") (name "unconnected-(22_X1-Pad26)") (class "Default")
      (node (ref "22_X1") (pin "26") (pinfunction "26_26") (pintype "passive"))
    )
    (net (code "117") (name "unconnected-(22_X1-Pad27)") (class "Default")
      (node (ref "22_X1") (pin "27") (pinfunction "27_27") (pintype "passive"))
    )
    (net (code "118") (name "unconnected-(22_X1-Pad28)") (class "Default")
      (node (ref "22_X1") (pin "28") (pinfunction "28_28") (pintype "passive"))
    )
    (net (code "119") (name "unconnected-(22_X1-Pad29)") (class "Default")
      (node (ref "22_X1") (pin "29") (pinfunction "29_29") (pintype "passive"))
    )
    (net (code "120") (name "unconnected-(22_X1-Pad30)") (class "Default")
      (node (ref "22_X1") (pin "30") (pinfunction "30_30") (pintype "passive"))
    )
    (net (code "121") (name "unconnected-(22_X1-Pad31)") (class "Default")
      (node (ref "22_X1") (pin "31") (pinfunction "31_31") (pintype "passive"))
    )
    (net (code "122") (name "unconnected-(22_X1-Pad32)") (class "Default")
      (node (ref "22_X1") (pin "32") (pinfunction "32_32") (pintype "passive"))
    )
    (net (code "123") (name "unconnected-(22_X1-Pad33)") (class "Default")
      (node (ref "22_X1") (pin "33") (pinfunction "33_33") (pintype "passive"))
    )
    (net (code "124") (name "unconnected-(22_X1-Pad34)") (class "Default")
      (node (ref "22_X1") (pin "34") (pinfunction "34_34") (pintype "passive+no_connect"))
    )
    (net (code "125") (name "unconnected-(22_X2-3-Pad25)") (class "Default")
      (node (ref "22_X2") (pin "25") (pinfunction "3_25") (pintype "passive"))
    )
    (net (code "126") (name "unconnected-(22_X2-7-Pad24)") (class "Default")
      (node (ref "22_X2") (pin "24") (pinfunction "7_24") (pintype "passive"))
    )
    (net (code "127") (name "unconnected-(22_X2-Pad17)") (class "Default")
      (node (ref "22_X2") (pin "17") (pinfunction "17_17") (pintype "passive+no_connect"))
    )
    (net (code "128") (name "unconnected-(22_X2-Pad18)") (class "Default")
      (node (ref "22_X2") (pin "18") (pinfunction "18_18") (pintype "passive"))
    )
    (net (code "129") (name "unconnected-(22_X2-Pad19)") (class "Default")
      (node (ref "22_X2") (pin "19") (pinfunction "19_19") (pintype "passive"))
    )
    (net (code "130") (name "unconnected-(22_X2-Pad20)") (class "Default")
      (node (ref "22_X2") (pin "20") (pinfunction "20_20") (pintype "passive"))
    )
    (net (code "131") (name "unconnected-(22_X2-Pad21)") (class "Default")
      (node (ref "22_X2") (pin "21") (pinfunction "21_21") (pintype "passive"))
    )
    (net (code "132") (name "unconnected-(22_X2-Pad22)") (class "Default")
      (node (ref "22_X2") (pin "22") (pinfunction "22_22") (pintype "passive"))
    )
    (net (code "133") (name "unconnected-(22_X2-Pad23)") (class "Default")
      (node (ref "22_X2") (pin "23") (pinfunction "23_23") (pintype "passive"))
    )
    (net (code "134") (name "unconnected-(22_X2-Pad26)") (class "Default")
      (node (ref "22_X2") (pin "26") (pinfunction "26_26") (pintype "passive"))
    )
    (net (code "135") (name "unconnected-(22_X2-Pad27)") (class "Default")
      (node (ref "22_X2") (pin "27") (pinfunction "27_27") (pintype "passive"))
    )
    (net (code "136") (name "unconnected-(22_X2-Pad28)") (class "Default")
      (node (ref "22_X2") (pin "28") (pinfunction "28_28") (pintype "passive"))
    )
    (net (code "137") (name "unconnected-(22_X2-Pad29)") (class "Default")
      (node (ref "22_X2") (pin "29") (pinfunction "29_29") (pintype "passive"))
    )
    (net (code "138") (name "unconnected-(22_X2-Pad30)") (class "Default")
      (node (ref "22_X2") (pin "30") (pinfunction "30_30") (pintype "passive"))
    )
    (net (code "139") (name "unconnected-(22_X2-Pad31)") (class "Default")
      (node (ref "22_X2") (pin "31") (pinfunction "31_31") (pintype "passive"))
    )
    (net (code "140") (name "unconnected-(22_X2-Pad32)") (class "Default")
      (node (ref "22_X2") (pin "32") (pinfunction "32_32") (pintype "passive"))
    )
    (net (code "141") (name "unconnected-(22_X2-Pad33)") (class "Default")
      (node (ref "22_X2") (pin "33") (pinfunction "33_33") (pintype "passive"))
    )
    (net (code "142") (name "unconnected-(22_X2-Pad34)") (class "Default")
      (node (ref "22_X2") (pin "34") (pinfunction "34_34") (pintype "passive+no_connect"))
    )
    (net (code "143") (name "unconnected-(22_X2-Pad49)") (class "Default")
      (node (ref "22_X2") (pin "49") (pinfunction "49_49") (pintype "passive"))
    )
    (net (code "144") (name "unconnected-(22_X2-Pad50)") (class "Default")
      (node (ref "22_X2") (pin "50") (pinfunction "50_50") (pintype "passive"))
    )
    (net (code "145") (name "unconnected-(23_X1-3-Pad25)") (class "Default")
      (node (ref "23_X1") (pin "25") (pinfunction "3_25") (pintype "passive"))
    )
    (net (code "146") (name "unconnected-(23_X1-7-Pad24)") (class "Default")
      (node (ref "23_X1") (pin "24") (pinfunction "7_24") (pintype "passive"))
    )
    (net (code "147") (name "unconnected-(23_X1-Pad17)") (class "Default")
      (node (ref "23_X1") (pin "17") (pinfunction "17_17") (pintype "passive+no_connect"))
    )
    (net (code "148") (name "unconnected-(23_X1-Pad18)") (class "Default")
      (node (ref "23_X1") (pin "18") (pinfunction "18_18") (pintype "passive"))
    )
    (net (code "149") (name "unconnected-(23_X1-Pad19)") (class "Default")
      (node (ref "23_X1") (pin "19") (pinfunction "19_19") (pintype "passive"))
    )
    (net (code "150") (name "unconnected-(23_X1-Pad20)") (class "Default")
      (node (ref "23_X1") (pin "20") (pinfunction "20_20") (pintype "passive"))
    )
    (net (code "151") (name "unconnected-(23_X1-Pad21)") (class "Default")
      (node (ref "23_X1") (pin "21") (pinfunction "21_21") (pintype "passive"))
    )
    (net (code "152") (name "unconnected-(23_X1-Pad22)") (class "Default")
      (node (ref "23_X1") (pin "22") (pinfunction "22_22") (pintype "passive"))
    )
    (net (code "153") (name "unconnected-(23_X1-Pad23)") (class "Default")
      (node (ref "23_X1") (pin "23") (pinfunction "23_23") (pintype "passive"))
    )
    (net (code "154") (name "unconnected-(23_X1-Pad26)") (class "Default")
      (node (ref "23_X1") (pin "26") (pinfunction "26_26") (pintype "passive"))
    )
    (net (code "155") (name "unconnected-(23_X1-Pad27)") (class "Default")
      (node (ref "23_X1") (pin "27") (pinfunction "27_27") (pintype "passive"))
    )
    (net (code "156") (name "unconnected-(23_X1-Pad28)") (class "Default")
      (node (ref "23_X1") (pin "28") (pinfunction "28_28") (pintype "passive"))
    )
    (net (code "157") (name "unconnected-(23_X1-Pad29)") (class "Default")
      (node (ref "23_X1") (pin "29") (pinfunction "29_29") (pintype "passive"))
    )
    (net (code "158") (name "unconnected-(23_X1-Pad30)") (class "Default")
      (node (ref "23_X1") (pin "30") (pinfunction "30_30") (pintype "passive"))
    )
    (net (code "159") (name "unconnected-(23_X1-Pad31)") (class "Default")
      (node (ref "23_X1") (pin "31") (pinfunction "31_31") (pintype "passive"))
    )
    (net (code "160") (name "unconnected-(23_X1-Pad32)") (class "Default")
      (node (ref "23_X1") (pin "32") (pinfunction "32_32") (pintype "passive"))
    )
    (net (code "161") (name "unconnected-(23_X1-Pad33)") (class "Default")
      (node (ref "23_X1") (pin "33") (pinfunction "33_33") (pintype "passive"))
    )
    (net (code "162") (name "unconnected-(23_X1-Pad34)") (class "Default")
      (node (ref "23_X1") (pin "34") (pinfunction "34_34") (pintype "passive+no_connect"))
    )
    (net (code "163") (name "unconnected-(23_X2-3-Pad25)") (class "Default")
      (node (ref "23_X2") (pin "25") (pinfunction "3_25") (pintype "passive"))
    )
    (net (code "164") (name "unconnected-(23_X2-7-Pad24)") (class "Default")
      (node (ref "23_X2") (pin "24") (pinfunction "7_24") (pintype "passive"))
    )
    (net (code "165") (name "unconnected-(23_X2-Pad17)") (class "Default")
      (node (ref "23_X2") (pin "17") (pinfunction "17_17") (pintype "passive+no_connect"))
    )
    (net (code "166") (name "unconnected-(23_X2-Pad18)") (class "Default")
      (node (ref "23_X2") (pin "18") (pinfunction "18_18") (pintype "passive"))
    )
    (net (code "167") (name "unconnected-(23_X2-Pad19)") (class "Default")
      (node (ref "23_X2") (pin "19") (pinfunction "19_19") (pintype "passive"))
    )
    (net (code "168") (name "unconnected-(23_X2-Pad20)") (class "Default")
      (node (ref "23_X2") (pin "20") (pinfunction "20_20") (pintype "passive"))
    )
    (net (code "169") (name "unconnected-(23_X2-Pad21)") (class "Default")
      (node (ref "23_X2") (pin "21") (pinfunction "21_21") (pintype "passive"))
    )
    (net (code "170") (name "unconnected-(23_X2-Pad22)") (class "Default")
      (node (ref "23_X2") (pin "22") (pinfunction "22_22") (pintype "passive"))
    )
    (net (code "171") (name "unconnected-(23_X2-Pad23)") (class "Default")
      (node (ref "23_X2") (pin "23") (pinfunction "23_23") (pintype "passive"))
    )
    (net (code "172") (name "unconnected-(23_X2-Pad26)") (class "Default")
      (node (ref "23_X2") (pin "26") (pinfunction "26_26") (pintype "passive"))
    )
    (net (code "173") (name "unconnected-(23_X2-Pad27)") (class "Default")
      (node (ref "23_X2") (pin "27") (pinfunction "27_27") (pintype "passive"))
    )
    (net (code "174") (name "unconnected-(23_X2-Pad28)") (class "Default")
      (node (ref "23_X2") (pin "28") (pinfunction "28_28") (pintype "passive"))
    )
    (net (code "175") (name "unconnected-(23_X2-Pad29)") (class "Default")
      (node (ref "23_X2") (pin "29") (pinfunction "29_29") (pintype "passive"))
    )
    (net (code "176") (name "unconnected-(23_X2-Pad30)") (class "Default")
      (node (ref "23_X2") (pin "30") (pinfunction "30_30") (pintype "passive"))
    )
    (net (code "177") (name "unconnected-(23_X2-Pad31)") (class "Default")
      (node (ref "23_X2") (pin "31") (pinfunction "31_31") (pintype "passive"))
    )
    (net (code "178") (name "unconnected-(23_X2-Pad32)") (class "Default")
      (node (ref "23_X2") (pin "32") (pinfunction "32_32") (pintype "passive"))
    )
    (net (code "179") (name "unconnected-(23_X2-Pad33)") (class "Default")
      (node (ref "23_X2") (pin "33") (pinfunction "33_33") (pintype "passive"))
    )
    (net (code "180") (name "unconnected-(23_X2-Pad34)") (class "Default")
      (node (ref "23_X2") (pin "34") (pinfunction "34_34") (pintype "passive+no_connect"))
    )
    (net (code "181") (name "unconnected-(23_X2-Pad49)") (class "Default")
      (node (ref "23_X2") (pin "49") (pinfunction "49_49") (pintype "passive"))
    )
    (net (code "182") (name "unconnected-(23_X2-Pad50)") (class "Default")
      (node (ref "23_X2") (pin "50") (pinfunction "50_50") (pintype "passive"))
    )
    (net (code "183") (name "unconnected-(24_X1-3-Pad25)") (class "Default")
      (node (ref "24_X1") (pin "25") (pinfunction "3_25") (pintype "passive"))
    )
    (net (code "184") (name "unconnected-(24_X1-7-Pad24)") (class "Default")
      (node (ref "24_X1") (pin "24") (pinfunction "7_24") (pintype "passive"))
    )
    (net (code "185") (name "unconnected-(24_X1-Pad17)") (class "Default")
      (node (ref "24_X1") (pin "17") (pinfunction "17_17") (pintype "passive+no_connect"))
    )
    (net (code "186") (name "unconnected-(24_X1-Pad18)") (class "Default")
      (node (ref "24_X1") (pin "18") (pinfunction "18_18") (pintype "passive"))
    )
    (net (code "187") (name "unconnected-(24_X1-Pad19)") (class "Default")
      (node (ref "24_X1") (pin "19") (pinfunction "19_19") (pintype "passive"))
    )
    (net (code "188") (name "unconnected-(24_X1-Pad20)") (class "Default")
      (node (ref "24_X1") (pin "20") (pinfunction "20_20") (pintype "passive"))
    )
    (net (code "189") (name "unconnected-(24_X1-Pad21)") (class "Default")
      (node (ref "24_X1") (pin "21") (pinfunction "21_21") (pintype "passive"))
    )
    (net (code "190") (name "unconnected-(24_X1-Pad22)") (class "Default")
      (node (ref "24_X1") (pin "22") (pinfunction "22_22") (pintype "passive"))
    )
    (net (code "191") (name "unconnected-(24_X1-Pad23)") (class "Default")
      (node (ref "24_X1") (pin "23") (pinfunction "23_23") (pintype "passive"))
    )
    (net (code "192") (name "unconnected-(24_X1-Pad26)") (class "Default")
      (node (ref "24_X1") (pin "26") (pinfunction "26_26") (pintype "passive"))
    )
    (net (code "193") (name "unconnected-(24_X1-Pad27)") (class "Default")
      (node (ref "24_X1") (pin "27") (pinfunction "27_27") (pintype "passive"))
    )
    (net (code "194") (name "unconnected-(24_X1-Pad28)") (class "Default")
      (node (ref "24_X1") (pin "28") (pinfunction "28_28") (pintype "passive"))
    )
    (net (code "195") (name "unconnected-(24_X1-Pad29)") (class "Default")
      (node (ref "24_X1") (pin "29") (pinfunction "29_29") (pintype "passive"))
    )
    (net (code "196") (name "unconnected-(24_X1-Pad30)") (class "Default")
      (node (ref "24_X1") (pin "30") (pinfunction "30_30") (pintype "passive"))
    )
    (net (code "197") (name "unconnected-(24_X1-Pad31)") (class "Default")
      (node (ref "24_X1") (pin "31") (pinfunction "31_31") (pintype "passive"))
    )
    (net (code "198") (name "unconnected-(24_X1-Pad32)") (class "Default")
      (node (ref "24_X1") (pin "32") (pinfunction "32_32") (pintype "passive"))
    )
    (net (code "199") (name "unconnected-(24_X1-Pad33)") (class "Default")
      (node (ref "24_X1") (pin "33") (pinfunction "33_33") (pintype "passive"))
    )
    (net (code "200") (name "unconnected-(24_X1-Pad34)") (class "Default")
      (node (ref "24_X1") (pin "34") (pinfunction "34_34") (pintype "passive+no_connect"))
    )
    (net (code "201") (name "unconnected-(24_X2-3-Pad25)") (class "Default")
      (node (ref "24_X2") (pin "25") (pinfunction "3_25") (pintype "passive"))
    )
    (net (code "202") (name "unconnected-(24_X2-7-Pad24)") (class "Default")
      (node (ref "24_X2") (pin "24") (pinfunction "7_24") (pintype "passive"))
    )
    (net (code "203") (name "unconnected-(24_X2-Pad17)") (class "Default")
      (node (ref "24_X2") (pin "17") (pinfunction "17_17") (pintype "passive+no_connect"))
    )
    (net (code "204") (name "unconnected-(24_X2-Pad18)") (class "Default")
      (node (ref "24_X2") (pin "18") (pinfunction "18_18") (pintype "passive"))
    )
    (net (code "205") (name "unconnected-(24_X2-Pad19)") (class "Default")
      (node (ref "24_X2") (pin "19") (pinfunction "19_19") (pintype "passive"))
    )
    (net (code "206") (name "unconnected-(24_X2-Pad20)") (class "Default")
      (node (ref "24_X2") (pin "20") (pinfunction "20_20") (pintype "passive"))
    )
    (net (code "207") (name "unconnected-(24_X2-Pad21)") (class "Default")
      (node (ref "24_X2") (pin "21") (pinfunction "21_21") (pintype "passive"))
    )
    (net (code "208") (name "unconnected-(24_X2-Pad22)") (class "Default")
      (node (ref "24_X2") (pin "22") (pinfunction "22_22") (pintype "passive"))
    )
    (net (code "209") (name "unconnected-(24_X2-Pad23)") (class "Default")
      (node (ref "24_X2") (pin "23") (pinfunction "23_23") (pintype "passive"))
    )
    (net (code "210") (name "unconnected-(24_X2-Pad26)") (class "Default")
      (node (ref "24_X2") (pin "26") (pinfunction "26_26") (pintype "passive"))
    )
    (net (code "211") (name "unconnected-(24_X2-Pad27)") (class "Default")
      (node (ref "24_X2") (pin "27") (pinfunction "27_27") (pintype "passive"))
    )
    (net (code "212") (name "unconnected-(24_X2-Pad28)") (class "Default")
      (node (ref "24_X2") (pin "28") (pinfunction "28_28") (pintype "passive"))
    )
    (net (code "213") (name "unconnected-(24_X2-Pad29)") (class "Default")
      (node (ref "24_X2") (pin "29") (pinfunction "29_29") (pintype "passive"))
    )
    (net (code "214") (name "unconnected-(24_X2-Pad30)") (class "Default")
      (node (ref "24_X2") (pin "30") (pinfunction "30_30") (pintype "passive"))
    )
    (net (code "215") (name "unconnected-(24_X2-Pad31)") (class "Default")
      (node (ref "24_X2") (pin "31") (pinfunction "31_31") (pintype "passive"))
    )
    (net (code "216") (name "unconnected-(24_X2-Pad32)") (class "Default")
      (node (ref "24_X2") (pin "32") (pinfunction "32_32") (pintype "passive"))
    )
    (net (code "217") (name "unconnected-(24_X2-Pad33)") (class "Default")
      (node (ref "24_X2") (pin "33") (pinfunction "33_33") (pintype "passive"))
    )
    (net (code "218") (name "unconnected-(24_X2-Pad34)") (class "Default")
      (node (ref "24_X2") (pin "34") (pinfunction "34_34") (pintype "passive+no_connect"))
    )
    (net (code "219") (name "unconnected-(24_X2-Pad49)") (class "Default")
      (node (ref "24_X2") (pin "49") (pinfunction "49_49") (pintype "passive"))
    )
    (net (code "220") (name "unconnected-(24_X2-Pad50)") (class "Default")
      (node (ref "24_X2") (pin "50") (pinfunction "50_50") (pintype "passive"))
    )
  )
)
